# 4_memory.net
KiCad netlist of a schematic drawn in Altium Designer
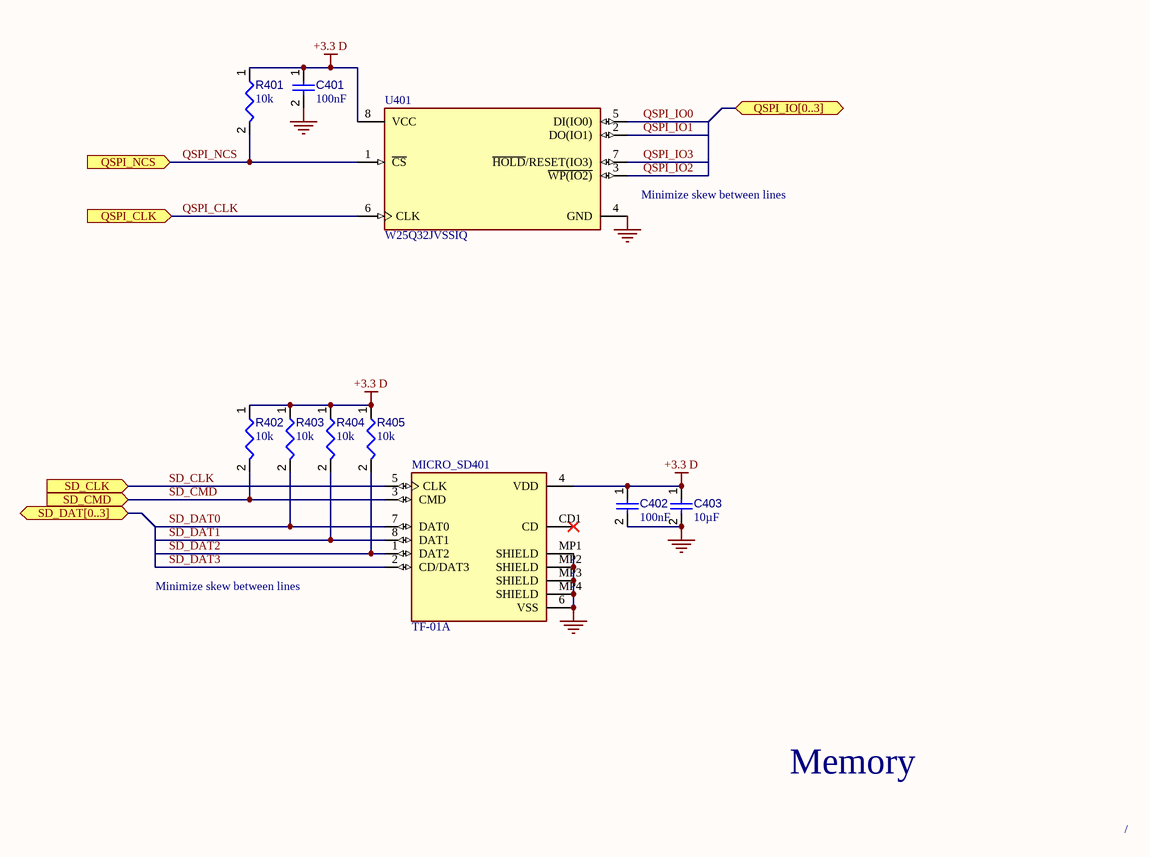
[diagram p0: 4 memory.SchDoc]

(export (version "E")
  (design (tool "Eeschema 10.0.6"))
  (components
    (comp (ref "C401")
      (value "100nF")
      (footprint "CAPC0402(1005)60_L")
      (description "Chip Capacitor, 100nF +/-20%, 25V, 0402, Thickness 0.6 mm")
      (fields (field (name "TOLERANCE") "10%") (field (name "Comment") "Capacitor 100nF +/-20% 25V 0402"))
      (libsource (lib "UBC Uncrewed Aircraft Systems") (part "CAP-NP-2"))
    )
    (comp (ref "C402")
      (value "100nF")
      (footprint "CAPC0402(1005)60_L")
      (description "Chip Capacitor, 100nF +/-20%, 25V, 0402, Thickness 0.6 mm")
      (fields (field (name "TOLERANCE") "10%") (field (name "Comment") "Capacitor 100nF +/-20% 25V 0402"))
      (libsource (lib "UBC Uncrewed Aircraft Systems") (part "CAP-NP-2"))
    )
    (comp (ref "C403")
      (value "10µF")
      (footprint "CAPC0603(1608)100_L")
      (description "Chip Capacitor, 10µF +/-20%, 10V, 0603, Thickness 1 mm")
      (fields (field (name "TOLERANCE") "10%") (field (name "Comment") "Capacitor 10µF +/-20% 10V 0603"))
      (libsource (lib "UBC Uncrewed Aircraft Systems") (part "CAP-NP-2"))
    )
    (comp (ref "MICRO_SD401")
      (value "TF-01A")
      (footprint "TF-01A")
      (description "Standard Card Edge Connectors")
      (fields (field (name "MF") "HRO Electronics Co., Ltd."))
      (libsource (lib "TF-01A") (part "TF-01A"))
    )
    (comp (ref "R401")
      (value "10k")
      (footprint "RESC0402(1005)_L")
      (description "Chip Resistor, 10 kOhms, +/-1 %, 63 mW, -55 to 125 degC, 0402")
      (fields (field (name "POWER") "63mW") (field (name "TOLERANCE") "1%"))
      (libsource (lib "UBC Uncrewed Aircraft Systems") (part "RES-2"))
    )
    (comp (ref "R402")
      (value "10k")
      (footprint "RESC0402(1005)_L")
      (description "Chip Resistor, 10 kOhms, +/-1 %, 63 mW, -55 to 125 degC, 0402")
      (fields (field (name "POWER") "63mW") (field (name "TOLERANCE") "1%"))
      (libsource (lib "UBC Uncrewed Aircraft Systems") (part "RES-2"))
    )
    (comp (ref "R403")
      (value "10k")
      (footprint "RESC0402(1005)_L")
      (description "Chip Resistor, 10 kOhms, +/-1 %, 63 mW, -55 to 125 degC, 0402")
      (fields (field (name "POWER") "63mW") (field (name "TOLERANCE") "1%"))
      (libsource (lib "UBC Uncrewed Aircraft Systems") (part "RES-2"))
    )
    (comp (ref "R404")
      (value "10k")
      (footprint "RESC0402(1005)_L")
      (description "Chip Resistor, 10 kOhms, +/-1 %, 63 mW, -55 to 125 degC, 0402")
      (fields (field (name "POWER") "63mW") (field (name "TOLERANCE") "1%"))
      (libsource (lib "UBC Uncrewed Aircraft Systems") (part "RES-2"))
    )
    (comp (ref "R405")
      (value "10k")
      (footprint "RESC0402(1005)_L")
      (description "Chip Resistor, 10 kOhms, +/-1 %, 63 mW, -55 to 125 degC, 0402")
      (fields (field (name "POWER") "63mW") (field (name "TOLERANCE") "1%"))
      (libsource (lib "UBC Uncrewed Aircraft Systems") (part "RES-2"))
    )
    (comp (ref "U401")
      (value "W25Q32JVSSIQ")
      (footprint "FP-SS-IPC_C")
      (description "IC FLASH 32M SPI 104MHZ 8SOIC")
      (fields
        (field (name "MANUFACTURER") "Winbond")
        (field (name "OCTOPART") "https://octopart.com/w25q32fvssig-winbond-23896462")
      )
      (libsource (lib "Altium Content Vault") (part "4804fbe011262506d6ec6a9051036b0"))
    )
  )
  (nets
    (net (code "1") (name "+3.3 D") (class "Default")
      (node (ref "C401") (pin "1") (pinfunction "1_1") (pintype "passive"))
      (node (ref "C402") (pin "1") (pinfunction "1_1") (pintype "passive"))
      (node (ref "C403") (pin "1") (pinfunction "1_1") (pintype "passive"))
      (node (ref "MICRO_SD401") (pin "4") (pinfunction "VDD_4") (pintype "power_in"))
      (node (ref "R401") (pin "1") (pinfunction "1_1") (pintype "passive"))
      (node (ref "R402") (pin "1") (pinfunction "1_1") (pintype "passive"))
      (node (ref "R403") (pin "1") (pinfunction "1_1") (pintype "passive"))
      (node (ref "R404") (pin "1") (pinfunction "1_1") (pintype "passive"))
      (node (ref "R405") (pin "1") (pinfunction "1_1") (pintype "passive"))
      (node (ref "U401") (pin "8") (pinfunction "VCC_8") (pintype "power_in"))
    )
    (net (code "2") (name "/QSPI_CLK") (class "Default")
      (node (ref "U401") (pin "6") (pinfunction "CLK_6") (pintype "input"))
    )
    (net (code "3") (name "/QSPI_IO0") (class "Default")
      (node (ref "U401") (pin "5") (pinfunction "DI(IO0)_5") (pintype "bidirectional"))
    )
    (net (code "4") (name "/QSPI_IO1") (class "Default")
      (node (ref "U401") (pin "2") (pinfunction "DO(IO1)_2") (pintype "bidirectional"))
    )
    (net (code "5") (name "/QSPI_IO2") (class "Default")
      (node (ref "U401") (pin "3") (pinfunction "~{WP(IO2)}_3") (pintype "bidirectional"))
    )
    (net (code "6") (name "/QSPI_IO3") (class "Default")
      (node (ref "U401") (pin "7") (pinfunction "~{HOLD}/RESET(IO3)_7") (pintype "bidirectional"))
    )
    (net (code "8") (name "/QSPI_NCS") (class "Default")
      (node (ref "R401") (pin "2") (pinfunction "2_2") (pintype "passive"))
      (node (ref "U401") (pin "1") (pinfunction "~{CS}_1") (pintype "input"))
    )
    (net (code "9") (name "/SD_CLK") (class "Default")
      (node (ref "MICRO_SD401") (pin "5") (pinfunction "CLK_5") (pintype "bidirectional"))
    )
    (net (code "10") (name "/SD_CMD") (class "Default")
      (node (ref "MICRO_SD401") (pin "3") (pinfunction "CMD_3") (pintype "bidirectional"))
      (node (ref "R402") (pin "2") (pinfunction "2_2") (pintype "passive"))
    )
    (net (code "11") (name "/SD_DAT0") (class "Default")
      (node (ref "MICRO_SD401") (pin "7") (pinfunction "DAT0_7") (pintype "bidirectional"))
      (node (ref "R403") (pin "2") (pinfunction "2_2") (pintype "passive"))
    )
    (net (code "12") (name "/SD_DAT1") (class "Default")
      (node (ref "MICRO_SD401") (pin "8") (pinfunction "DAT1_8") (pintype "bidirectional"))
      (node (ref "R404") (pin "2") (pinfunction "2_2") (pintype "passive"))
    )
    (net (code "13") (name "/SD_DAT2") (class "Default")
      (node (ref "MICRO_SD401") (pin "1") (pinfunction "DAT2_1") (pintype "bidirectional"))
      (node (ref "R405") (pin "2") (pinfunction "2_2") (pintype "passive"))
    )
    (net (code "14") (name "/SD_DAT3") (class "Default")
      (node (ref "MICRO_SD401") (pin "2") (pinfunction "CD/DAT3_2") (pintype "bidirectional"))
    )
    (net (code "16") (name "GND") (class "Default")
      (node (ref "C401") (pin "2") (pinfunction "2_2") (pintype "passive"))
      (node (ref "C402") (pin "2") (pinfunction "2_2") (pintype "passive"))
      (node (ref "C403") (pin "2") (pinfunction "2_2") (pintype "passive"))
      (node (ref "MICRO_SD401") (pin "6") (pinfunction "VSS_6") (pintype "power_in"))
      (node (ref "MICRO_SD401") (pin "MP1") (pinfunction "SHIELD_MP1") (pintype "power_in"))
      (node (ref "MICRO_SD401") (pin "MP2") (pinfunction "SHIELD_MP2") (pintype "power_in"))
      (node (ref "MICRO_SD401") (pin "MP3") (pinfunction "SHIELD_MP3") (pintype "power_in"))
      (node (ref "MICRO_SD401") (pin "MP4") (pinfunction "SHIELD_MP4") (pintype "power_in"))
      (node (ref "U401") (pin "4") (pinfunction "GND_4") (pintype "power_in"))
    )
    (net (code "17") (name "unconnected-(MICRO_SD401-CD-PadCD1)") (class "Default")
      (node (ref "MICRO_SD401") (pin "CD1") (pinfunction "CD_CD1") (pintype "passive+no_connect"))
    )
  )
)
